# 150218_AriloRX_REV2_0_0.net
KiCad netlist of a schematic drawn in EAGLE
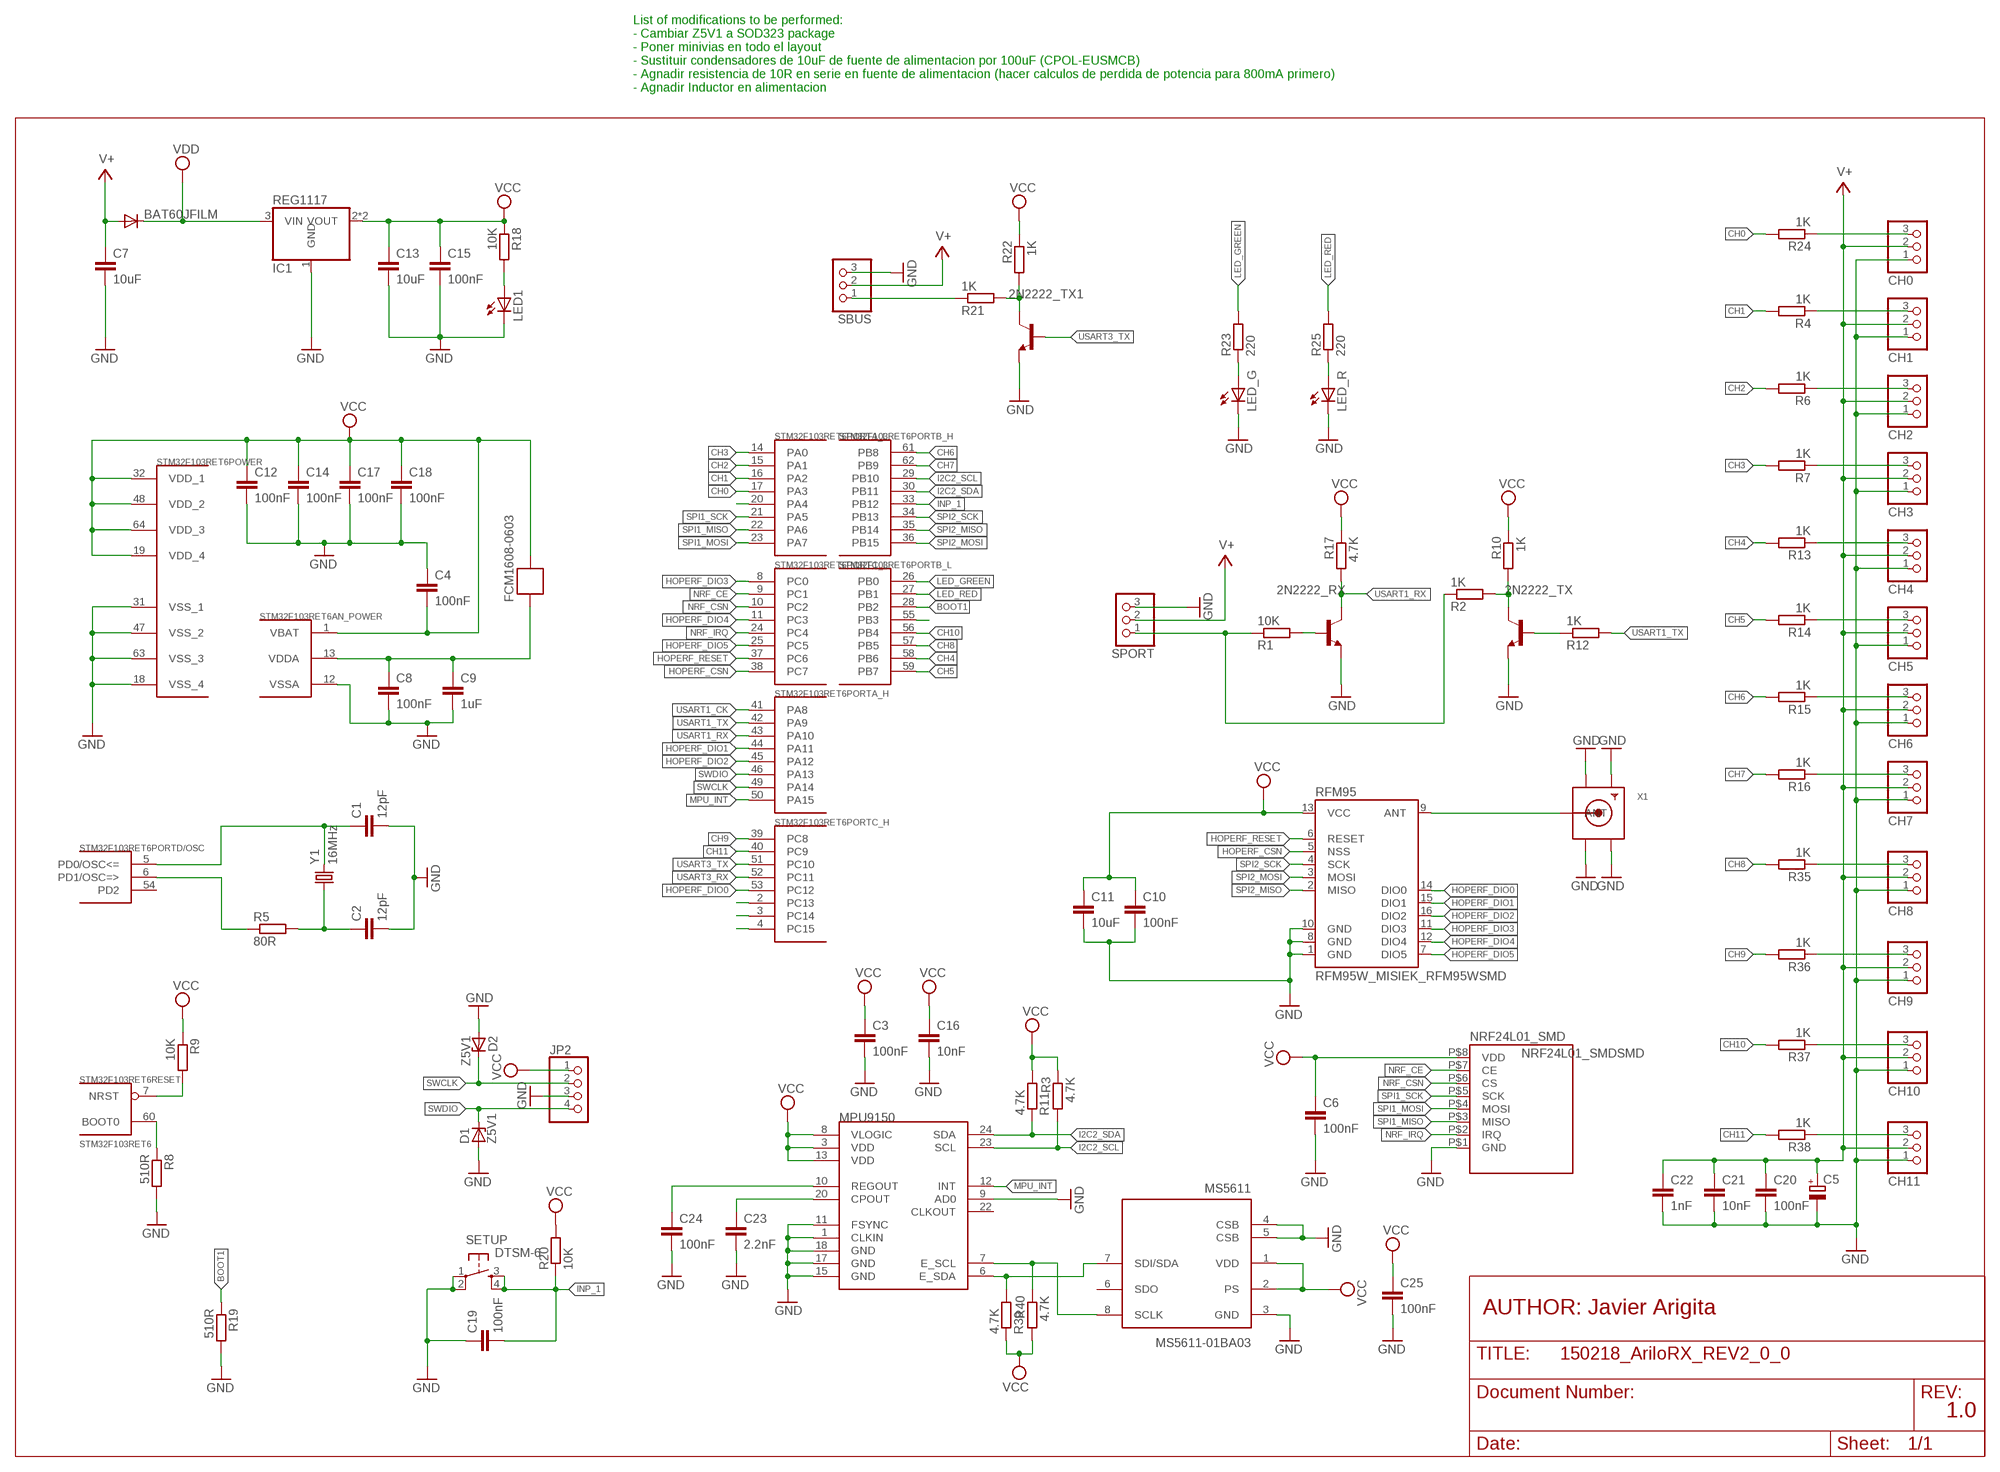
[diagram p0: schematic, sheet 1]

(export (version "E")
  (design (tool "Eeschema 10.0.6"))
  (components
    (comp (ref "2N2222_RX")
      (value "MMBT2222ALT1-NPN-SOT23-BEC")
      (footprint "eagle-import:SOT23-BEC")
      (libsource (lib "eagle-import") (part "-NPN-SOT23-BECMMBT2222ALT1"))
    )
    (comp (ref "2N2222_TX")
      (value "MMBT2222ALT1-NPN-SOT23-BEC")
      (footprint "eagle-import:SOT23-BEC")
      (libsource (lib "eagle-import") (part "-NPN-SOT23-BECMMBT2222ALT1"))
    )
    (comp (ref "2N2222_TX1")
      (value "MMBT2222ALT1-NPN-SOT23-BEC")
      (footprint "eagle-import:SOT23-BEC")
      (libsource (lib "eagle-import") (part "-NPN-SOT23-BECMMBT2222ALT1"))
    )
    (comp (ref "BAT60JFILM")
      (value "DIODE-SOD323-R")
      (footprint "eagle-import:SOD323-R")
      (libsource (lib "eagle-import") (part "DIODE-SOD323-R"))
    )
    (comp (ref "C1")
      (value "12pF")
      (footprint "eagle-import:RESISTOR_C0603")
      (libsource (lib "eagle-import") (part "RESISTOR_C-EUC0603"))
    )
    (comp (ref "C2")
      (value "12pF")
      (footprint "eagle-import:RESISTOR_C0603")
      (libsource (lib "eagle-import") (part "RESISTOR_C-EUC0603"))
    )
    (comp (ref "C3")
      (value "100nF")
      (footprint "eagle-import:RESISTOR_C0603")
      (libsource (lib "eagle-import") (part "RESISTOR_C-EUC0603"))
    )
    (comp (ref "C4")
      (value "100nF")
      (footprint "eagle-import:RESISTOR_C0603")
      (libsource (lib "eagle-import") (part "RESISTOR_C-EUC0603"))
    )
    (comp (ref "C5")
      (value "CPOL-EUSMCB")
      (footprint "eagle-import:SMC_B")
      (libsource (lib "eagle-import") (part "CPOL-EUSMCB"))
    )
    (comp (ref "C6")
      (value "100nF")
      (footprint "eagle-import:RESISTOR_C0603")
      (libsource (lib "eagle-import") (part "RESISTOR_C-EUC0603"))
    )
    (comp (ref "C7")
      (value "10uF")
      (footprint "eagle-import:RESISTOR_C3216")
      (libsource (lib "eagle-import") (part "RESISTOR_C-EUC3216"))
    )
    (comp (ref "C8")
      (value "100nF")
      (footprint "eagle-import:RESISTOR_C0603")
      (libsource (lib "eagle-import") (part "RESISTOR_C-EUC0603"))
    )
    (comp (ref "C9")
      (value "1uF")
      (footprint "eagle-import:RESISTOR_C0603")
      (libsource (lib "eagle-import") (part "RESISTOR_C-EUC0603"))
    )
    (comp (ref "C10")
      (value "100nF")
      (footprint "eagle-import:RESISTOR_C0603")
      (libsource (lib "eagle-import") (part "RESISTOR_C-EUC0603"))
    )
    (comp (ref "C11")
      (value "10uF")
      (footprint "eagle-import:RESISTOR_C3216")
      (libsource (lib "eagle-import") (part "RESISTOR_C-EUC3216"))
    )
    (comp (ref "C12")
      (value "100nF")
      (footprint "eagle-import:RESISTOR_C0603")
      (libsource (lib "eagle-import") (part "RESISTOR_C-EUC0603"))
    )
    (comp (ref "C13")
      (value "10uF")
      (footprint "eagle-import:RESISTOR_C3216")
      (libsource (lib "eagle-import") (part "RESISTOR_C-EUC3216"))
    )
    (comp (ref "C14")
      (value "100nF")
      (footprint "eagle-import:RESISTOR_C0603")
      (libsource (lib "eagle-import") (part "RESISTOR_C-EUC0603"))
    )
    (comp (ref "C15")
      (value "100nF")
      (footprint "eagle-import:RESISTOR_C0603")
      (libsource (lib "eagle-import") (part "RESISTOR_C-EUC0603"))
    )
    (comp (ref "C16")
      (value "10nF")
      (footprint "eagle-import:RESISTOR_C0603")
      (libsource (lib "eagle-import") (part "RESISTOR_C-EUC0603"))
    )
    (comp (ref "C17")
      (value "100nF")
      (footprint "eagle-import:RESISTOR_C0603")
      (libsource (lib "eagle-import") (part "RESISTOR_C-EUC0603"))
    )
    (comp (ref "C18")
      (value "100nF")
      (footprint "eagle-import:RESISTOR_C0603")
      (libsource (lib "eagle-import") (part "RESISTOR_C-EUC0603"))
    )
    (comp (ref "C19")
      (value "100nF")
      (footprint "eagle-import:RESISTOR_C0603")
      (libsource (lib "eagle-import") (part "RESISTOR_C-EUC0603"))
    )
    (comp (ref "C20")
      (value "100nF")
      (footprint "eagle-import:RESISTOR_C0603")
      (libsource (lib "eagle-import") (part "RESISTOR_C-EUC0603"))
    )
    (comp (ref "C21")
      (value "10nF")
      (footprint "eagle-import:RESISTOR_C0603")
      (libsource (lib "eagle-import") (part "RESISTOR_C-EUC0603"))
    )
    (comp (ref "C22")
      (value "1nF")
      (footprint "eagle-import:RESISTOR_C0603")
      (libsource (lib "eagle-import") (part "RESISTOR_C-EUC0603"))
    )
    (comp (ref "C23")
      (value "2.2nF")
      (footprint "eagle-import:RESISTOR_C0603")
      (libsource (lib "eagle-import") (part "RESISTOR_C-EUC0603"))
    )
    (comp (ref "C24")
      (value "100nF")
      (footprint "eagle-import:RESISTOR_C0603")
      (libsource (lib "eagle-import") (part "RESISTOR_C-EUC0603"))
    )
    (comp (ref "C25")
      (value "100nF")
      (footprint "eagle-import:RESISTOR_C0603")
      (libsource (lib "eagle-import") (part "RESISTOR_C-EUC0603"))
    )
    (comp (ref "CH0")
      (value "PINHD-1X3")
      (footprint "eagle-import:1X03")
      (libsource (lib "eagle-import") (part "pinhead_rc_PINHD-1X3"))
    )
    (comp (ref "CH1")
      (value "PINHD-1X3")
      (footprint "eagle-import:1X03")
      (libsource (lib "eagle-import") (part "pinhead_rc_PINHD-1X3"))
    )
    (comp (ref "CH2")
      (value "PINHD-1X3")
      (footprint "eagle-import:1X03")
      (libsource (lib "eagle-import") (part "pinhead_rc_PINHD-1X3"))
    )
    (comp (ref "CH3")
      (value "PINHD-1X3")
      (footprint "eagle-import:1X03")
      (libsource (lib "eagle-import") (part "pinhead_rc_PINHD-1X3"))
    )
    (comp (ref "CH4")
      (value "PINHD-1X3")
      (footprint "eagle-import:1X03")
      (libsource (lib "eagle-import") (part "pinhead_rc_PINHD-1X3"))
    )
    (comp (ref "CH5")
      (value "PINHD-1X3")
      (footprint "eagle-import:1X03")
      (libsource (lib "eagle-import") (part "pinhead_rc_PINHD-1X3"))
    )
    (comp (ref "CH6")
      (value "PINHD-1X3")
      (footprint "eagle-import:1X03")
      (libsource (lib "eagle-import") (part "pinhead_rc_PINHD-1X3"))
    )
    (comp (ref "CH7")
      (value "PINHD-1X3")
      (footprint "eagle-import:1X03")
      (libsource (lib "eagle-import") (part "pinhead_rc_PINHD-1X3"))
    )
    (comp (ref "CH8")
      (value "PINHD-1X3")
      (footprint "eagle-import:1X03")
      (libsource (lib "eagle-import") (part "pinhead_rc_PINHD-1X3"))
    )
    (comp (ref "CH9")
      (value "PINHD-1X3")
      (footprint "eagle-import:1X03")
      (libsource (lib "eagle-import") (part "pinhead_rc_PINHD-1X3"))
    )
    (comp (ref "CH10")
      (value "PINHD-1X3")
      (footprint "eagle-import:1X03")
      (libsource (lib "eagle-import") (part "pinhead_rc_PINHD-1X3"))
    )
    (comp (ref "CH11")
      (value "PINHD-1X3")
      (footprint "eagle-import:1X03")
      (libsource (lib "eagle-import") (part "pinhead_rc_PINHD-1X3"))
    )
    (comp (ref "D1")
      (value "Z5V1")
      (footprint "eagle-import:SOD80C")
      (libsource (lib "eagle-import") (part "ZENER-DIODESOD80C"))
    )
    (comp (ref "D2")
      (value "Z5V1")
      (footprint "eagle-import:SOD80C")
      (libsource (lib "eagle-import") (part "ZENER-DIODESOD80C"))
    )
    (comp (ref "FCM1608-0603")
      (value "FERRITE-BEAD")
      (footprint "eagle-import:R0603")
      (libsource (lib "eagle-import") (part "FERRITE-BEAD"))
    )
    (comp (ref "IC1")
      (value "REG1117")
      (footprint "eagle-import:SOT223")
      (libsource (lib "eagle-import") (part "REG1117"))
    )
    (comp (ref "JP2")
      (value "PINHD-1X4")
      (footprint "eagle-import:1X04")
      (libsource (lib "eagle-import") (part "PINHD-1X4"))
    )
    (comp (ref "LED1")
      (value "LED_LEDCHIP-LED0603")
      (footprint "eagle-import:LED_CHIP-LED0603")
      (libsource (lib "eagle-import") (part "LED_LEDCHIP-LED0603"))
    )
    (comp (ref "LED_G")
      (value "LEDCHIP-LED0603")
      (footprint "eagle-import:CHIP-LED0603")
      (libsource (lib "eagle-import") (part "LEDCHIP-LED0603"))
    )
    (comp (ref "LED_R")
      (value "LEDCHIP-LED0603")
      (footprint "eagle-import:CHIP-LED0603")
      (libsource (lib "eagle-import") (part "LEDCHIP-LED0603"))
    )
    (comp (ref "MPU9150")
      (value "MPU-9150QFN-24-NP")
      (footprint "eagle-import:QFN-24-NP")
      (libsource (lib "eagle-import") (part "MPU-9150QFN-24-NP"))
    )
    (comp (ref "MS5611")
      (value "MS5611-01BA03")
      (footprint "eagle-import:SON125P300X500X100-8N")
      (libsource (lib "eagle-import") (part "MS5611-01BA03"))
    )
    (comp (ref "NRF24L01_SMD")
      (value "NRF24L01_SMDSMD")
      (footprint "eagle-import:NRF24L01_SMD")
      (libsource (lib "eagle-import") (part "NRF24L01_SMDSMD"))
    )
    (comp (ref "R1")
      (value "10K")
      (footprint "eagle-import:RCL_R0603")
      (libsource (lib "eagle-import") (part "RCL_R-EU_R0603"))
    )
    (comp (ref "R2")
      (value "1K")
      (footprint "eagle-import:RCL_R0603")
      (libsource (lib "eagle-import") (part "RCL_R-EU_R0603"))
    )
    (comp (ref "R3")
      (value "4.7K")
      (footprint "eagle-import:RCL_R0603")
      (libsource (lib "eagle-import") (part "RCL_R-EU_R0603"))
    )
    (comp (ref "R4")
      (value "1K")
      (footprint "eagle-import:RCL_R0603")
      (libsource (lib "eagle-import") (part "RCL_R-EU_R0603"))
    )
    (comp (ref "R5")
      (value "80R")
      (footprint "eagle-import:RCL_R0603")
      (libsource (lib "eagle-import") (part "RCL_R-EU_R0603"))
    )
    (comp (ref "R6")
      (value "1K")
      (footprint "eagle-import:RCL_R0603")
      (libsource (lib "eagle-import") (part "RCL_R-EU_R0603"))
    )
    (comp (ref "R7")
      (value "1K")
      (footprint "eagle-import:RCL_R0603")
      (libsource (lib "eagle-import") (part "RCL_R-EU_R0603"))
    )
    (comp (ref "R8")
      (value "510R")
      (footprint "eagle-import:RCL_R0603")
      (libsource (lib "eagle-import") (part "RCL_R-EU_R0603"))
    )
    (comp (ref "R9")
      (value "10K")
      (footprint "eagle-import:RCL_R0603")
      (libsource (lib "eagle-import") (part "RCL_R-EU_R0603"))
    )
    (comp (ref "R10")
      (value "1K")
      (footprint "eagle-import:RCL_R0603")
      (libsource (lib "eagle-import") (part "RCL_R-EU_R0603"))
    )
    (comp (ref "R11")
      (value "4.7K")
      (footprint "eagle-import:RCL_R0603")
      (libsource (lib "eagle-import") (part "RCL_R-EU_R0603"))
    )
    (comp (ref "R12")
      (value "1K")
      (footprint "eagle-import:RCL_R0603")
      (libsource (lib "eagle-import") (part "RCL_R-EU_R0603"))
    )
    (comp (ref "R13")
      (value "1K")
      (footprint "eagle-import:RCL_R0603")
      (libsource (lib "eagle-import") (part "RCL_R-EU_R0603"))
    )
    (comp (ref "R14")
      (value "1K")
      (footprint "eagle-import:RCL_R0603")
      (libsource (lib "eagle-import") (part "RCL_R-EU_R0603"))
    )
    (comp (ref "R15")
      (value "1K")
      (footprint "eagle-import:RCL_R0603")
      (libsource (lib "eagle-import") (part "RCL_R-EU_R0603"))
    )
    (comp (ref "R16")
      (value "1K")
      (footprint "eagle-import:RCL_R0603")
      (libsource (lib "eagle-import") (part "RCL_R-EU_R0603"))
    )
    (comp (ref "R17")
      (value "4.7K")
      (footprint "eagle-import:RCL_R0603")
      (libsource (lib "eagle-import") (part "RCL_R-EU_R0603"))
    )
    (comp (ref "R18")
      (value "10K")
      (footprint "eagle-import:RCL_R0603")
      (libsource (lib "eagle-import") (part "RCL_R-EU_R0603"))
    )
    (comp (ref "R19")
      (value "510R")
      (footprint "eagle-import:RCL_R0603")
      (libsource (lib "eagle-import") (part "RCL_R-EU_R0603"))
    )
    (comp (ref "R20")
      (value "10K")
      (footprint "eagle-import:RCL_R0603")
      (libsource (lib "eagle-import") (part "RCL_R-EU_R0603"))
    )
    (comp (ref "R21")
      (value "1K")
      (footprint "eagle-import:RCL_R0603")
      (libsource (lib "eagle-import") (part "RCL_R-EU_R0603"))
    )
    (comp (ref "R22")
      (value "1K")
      (footprint "eagle-import:RCL_R0603")
      (libsource (lib "eagle-import") (part "RCL_R-EU_R0603"))
    )
    (comp (ref "R23")
      (value "220")
      (footprint "eagle-import:RCL_R0603")
      (libsource (lib "eagle-import") (part "RCL_R-EU_R0603"))
    )
    (comp (ref "R24")
      (value "1K")
      (footprint "eagle-import:RCL_R0603")
      (libsource (lib "eagle-import") (part "RCL_R-EU_R0603"))
    )
    (comp (ref "R25")
      (value "220")
      (footprint "eagle-import:RCL_R0603")
      (libsource (lib "eagle-import") (part "RCL_R-EU_R0603"))
    )
    (comp (ref "R35")
      (value "1K")
      (footprint "eagle-import:RCL_R0603")
      (libsource (lib "eagle-import") (part "RCL_R-EU_R0603"))
    )
    (comp (ref "R36")
      (value "1K")
      (footprint "eagle-import:RCL_R0603")
      (libsource (lib "eagle-import") (part "RCL_R-EU_R0603"))
    )
    (comp (ref "R37")
      (value "1K")
      (footprint "eagle-import:RCL_R0603")
      (libsource (lib "eagle-import") (part "RCL_R-EU_R0603"))
    )
    (comp (ref "R38")
      (value "1K")
      (footprint "eagle-import:RCL_R0603")
      (libsource (lib "eagle-import") (part "RCL_R-EU_R0603"))
    )
    (comp (ref "R39")
      (value "4.7K")
      (footprint "eagle-import:RCL_R0603")
      (libsource (lib "eagle-import") (part "RCL_R-EU_R0603"))
    )
    (comp (ref "R40")
      (value "4.7K")
      (footprint "eagle-import:RCL_R0603")
      (libsource (lib "eagle-import") (part "RCL_R-EU_R0603"))
    )
    (comp (ref "RFM95")
      (value "RFM95W_MISIEK_RFM95WSMD")
      (footprint "eagle-import:RFM95W_MISIEK_RFM95W_SMD")
      (libsource (lib "eagle-import") (part "RFM95W_MISIEK_RFM95WSMD"))
    )
    (comp (ref "SBUS")
      (value "PINHD-1X3")
      (footprint "eagle-import:1X03")
      (libsource (lib "eagle-import") (part "PINHD-1X3"))
    )
    (comp (ref "SETUP")
      (value "DTSM-6")
      (footprint "eagle-import:DTSM-6")
      (libsource (lib "eagle-import") (part "DTSM-6"))
    )
    (comp (ref "SPORT")
      (value "PINHD-1X3")
      (footprint "eagle-import:1X03")
      (libsource (lib "eagle-import") (part "PINHD-1X3"))
    )
    (comp (ref "STM32F103RET6")
      (value "STM32F103RET6")
      (footprint "eagle-import:TQFP64")
      (libsource (lib "eagle-import") (part "STM32F10XRXT6"))
    )
    (comp (ref "X1")
      (value "SMACONNECTOR_EDGE")
      (footprint "eagle-import:SMA_EDGELAUNCH")
      (libsource (lib "eagle-import") (part "SMACONNECTOR_EDGE"))
    )
    (comp (ref "Y1")
      (value "16MHz")
      (footprint "eagle-import:CRYSTAL-SMD-5X3")
      (libsource (lib "eagle-import") (part "CRYSTAL5X3"))
    )
  )
  (nets
    (net (code "1") (name "BOOT1") (class "Default")
      (node (ref "R19") (pin "1") (pinfunction "1_1") (pintype "passive"))
      (node (ref "STM32F103RET6") (pin "28") (pinfunction "PB2_28") (pintype "bidirectional"))
    )
    (net (code "2") (name "CH0") (class "Default")
      (node (ref "R24") (pin "2") (pinfunction "2_2") (pintype "passive"))
      (node (ref "STM32F103RET6") (pin "17") (pinfunction "PA3_17") (pintype "bidirectional"))
    )
    (net (code "3") (name "CH1") (class "Default")
      (node (ref "R4") (pin "2") (pinfunction "2_2") (pintype "passive"))
      (node (ref "STM32F103RET6") (pin "16") (pinfunction "PA2_16") (pintype "bidirectional"))
    )
    (net (code "4") (name "CH2") (class "Default")
      (node (ref "R6") (pin "2") (pinfunction "2_2") (pintype "passive"))
      (node (ref "STM32F103RET6") (pin "15") (pinfunction "PA1_15") (pintype "bidirectional"))
    )
    (net (code "5") (name "CH3") (class "Default")
      (node (ref "R7") (pin "2") (pinfunction "2_2") (pintype "passive"))
      (node (ref "STM32F103RET6") (pin "14") (pinfunction "PA0_14") (pintype "bidirectional"))
    )
    (net (code "6") (name "CH4") (class "Default")
      (node (ref "R13") (pin "2") (pinfunction "2_2") (pintype "passive"))
      (node (ref "STM32F103RET6") (pin "58") (pinfunction "PB6_58") (pintype "bidirectional"))
    )
    (net (code "7") (name "CH5") (class "Default")
      (node (ref "R14") (pin "2") (pinfunction "2_2") (pintype "passive"))
      (node (ref "STM32F103RET6") (pin "59") (pinfunction "PB7_59") (pintype "bidirectional"))
    )
    (net (code "8") (name "CH6") (class "Default")
      (node (ref "R15") (pin "2") (pinfunction "2_2") (pintype "passive"))
      (node (ref "STM32F103RET6") (pin "61") (pinfunction "PB8_61") (pintype "bidirectional"))
    )
    (net (code "9") (name "CH7") (class "Default")
      (node (ref "R16") (pin "2") (pinfunction "2_2") (pintype "passive"))
      (node (ref "STM32F103RET6") (pin "62") (pinfunction "PB9_62") (pintype "bidirectional"))
    )
    (net (code "10") (name "CH8") (class "Default")
      (node (ref "R35") (pin "2") (pinfunction "2_2") (pintype "passive"))
      (node (ref "STM32F103RET6") (pin "57") (pinfunction "PB5_57") (pintype "bidirectional"))
    )
    (net (code "11") (name "CH9") (class "Default")
      (node (ref "R36") (pin "2") (pinfunction "2_2") (pintype "passive"))
      (node (ref "STM32F103RET6") (pin "39") (pinfunction "PC8_39") (pintype "bidirectional"))
    )
    (net (code "12") (name "CH10") (class "Default")
      (node (ref "R37") (pin "2") (pinfunction "2_2") (pintype "passive"))
      (node (ref "STM32F103RET6") (pin "56") (pinfunction "PB4_56") (pintype "bidirectional"))
    )
    (net (code "13") (name "CH11") (class "Default")
      (node (ref "R38") (pin "2") (pinfunction "2_2") (pintype "passive"))
      (node (ref "STM32F103RET6") (pin "40") (pinfunction "PC9_40") (pintype "bidirectional"))
    )
    (net (code "14") (name "GND") (class "Default")
      (node (ref "2N2222_RX") (pin "E") (pinfunction "E_E") (pintype "passive"))
      (node (ref "2N2222_TX") (pin "E") (pinfunction "E_E") (pintype "passive"))
      (node (ref "2N2222_TX1") (pin "E") (pinfunction "E_E") (pintype "passive"))
      (node (ref "C1") (pin "2") (pinfunction "2_2") (pintype "passive"))
      (node (ref "C10") (pin "2") (pinfunction "2_2") (pintype "passive"))
      (node (ref "C11") (pin "2") (pinfunction "2_2") (pintype "passive"))
      (node (ref "C12") (pin "2") (pinfunction "2_2") (pintype "passive"))
      (node (ref "C13") (pin "2") (pinfunction "2_2") (pintype "passive"))
      (node (ref "C14") (pin "2") (pinfunction "2_2") (pintype "passive"))
      (node (ref "C15") (pin "2") (pinfunction "2_2") (pintype "passive"))
      (node (ref "C16") (pin "2") (pinfunction "2_2") (pintype "passive"))
      (node (ref "C17") (pin "2") (pinfunction "2_2") (pintype "passive"))
      (node (ref "C18") (pin "2") (pinfunction "2_2") (pintype "passive"))
      (node (ref "C19") (pin "1") (pinfunction "1_1") (pintype "passive"))
      (node (ref "C2") (pin "2") (pinfunction "2_2") (pintype "passive"))
      (node (ref "C20") (pin "2") (pinfunction "2_2") (pintype "passive"))
      (node (ref "C21") (pin "2") (pinfunction "2_2") (pintype "passive"))
      (node (ref "C22") (pin "2") (pinfunction "2_2") (pintype "passive"))
      (node (ref "C23") (pin "2") (pinfunction "2_2") (pintype "passive"))
      (node (ref "C24") (pin "2") (pinfunction "2_2") (pintype "passive"))
      (node (ref "C25") (pin "2") (pinfunction "2_2") (pintype "passive"))
      (node (ref "C3") (pin "2") (pinfunction "2_2") (pintype "passive"))
      (node (ref "C4") (pin "1") (pinfunction "1_1") (pintype "passive"))
      (node (ref "C5") (pin "-") (pinfunction "-_-") (pintype "passive"))
      (node (ref "C6") (pin "2") (pinfunction "2_2") (pintype "passive"))
      (node (ref "C7") (pin "2") (pinfunction "2_2") (pintype "passive"))
      (node (ref "C8") (pin "2") (pinfunction "2_2") (pintype "passive"))
      (node (ref "C9") (pin "2") (pinfunction "2_2") (pintype "passive"))
      (node (ref "CH0") (pin "1") (pinfunction "1_1") (pintype "passive"))
      (node (ref "CH1") (pin "1") (pinfunction "1_1") (pintype "passive"))
      (node (ref "CH10") (pin "1") (pinfunction "1_1") (pintype "passive"))
      (node (ref "CH11") (pin "1") (pinfunction "1_1") (pintype "passive"))
      (node (ref "CH2") (pin "1") (pinfunction "1_1") (pintype "passive"))
      (node (ref "CH3") (pin "1") (pinfunction "1_1") (pintype "passive"))
      (node (ref "CH4") (pin "1") (pinfunction "1_1") (pintype "passive"))
      (node (ref "CH5") (pin "1") (pinfunction "1_1") (pintype "passive"))
      (node (ref "CH6") (pin "1") (pinfunction "1_1") (pintype "passive"))
      (node (ref "CH7") (pin "1") (pinfunction "1_1") (pintype "passive"))
      (node (ref "CH8") (pin "1") (pinfunction "1_1") (pintype "passive"))
      (node (ref "CH9") (pin "1") (pinfunction "1_1") (pintype "passive"))
      (node (ref "D1") (pin "A") (pinfunction "A_A") (pintype "passive"))
      (node (ref "D2") (pin "A") (pinfunction "A_A") (pintype "passive"))
      (node (ref "IC1") (pin "1") (pinfunction "GND_1") (pintype "power_in"))
      (node (ref "JP2") (pin "3") (pinfunction "3_3") (pintype "passive"))
      (node (ref "LED1") (pin "C") (pinfunction "C_C") (pintype "passive"))
      (node (ref "LED_G") (pin "C") (pinfunction "C_C") (pintype "passive"))
      (node (ref "LED_R") (pin "C") (pinfunction "C_C") (pintype "passive"))
      (node (ref "MPU9150") (pin "1") (pinfunction "CLKIN_1") (pintype "bidirectional"))
      (node (ref "MPU9150") (pin "11") (pinfunction "FSYNC_11") (pintype "bidirectional"))
      (node (ref "MPU9150") (pin "15") (pinfunction "GND_15") (pintype "bidirectional"))
      (node (ref "MPU9150") (pin "17") (pinfunction "GND_17") (pintype "bidirectional"))
      (node (ref "MPU9150") (pin "18") (pinfunction "GND_18") (pintype "bidirectional"))
      (node (ref "MPU9150") (pin "9") (pinfunction "AD0_9") (pintype "bidirectional"))
      (node (ref "MS5611") (pin "3") (pinfunction "GND_3") (pintype "power_in"))
      (node (ref "MS5611") (pin "4") (pinfunction "CSB_4") (pintype "input"))
      (node (ref "MS5611") (pin "5") (pinfunction "CSB_5") (pintype "input"))
      (node (ref "NRF24L01_SMD") (pin "P$1") (pinfunction "GND_P$1") (pintype "power_in"))
      (node (ref "R19") (pin "2") (pinfunction "2_2") (pintype "passive"))
      (node (ref "R8") (pin "2") (pinfunction "2_2") (pintype "passive"))
      (node (ref "RFM95") (pin "1") (pinfunction "GND_1") (pintype "power_in"))
      (node (ref "RFM95") (pin "10") (pinfunction "GND_10") (pintype "power_in"))
      (node (ref "RFM95") (pin "8") (pinfunction "GND_8") (pintype "power_in"))
      (node (ref "SBUS") (pin "3") (pinfunction "3_3") (pintype "passive"))
      (node (ref "SETUP") (pin "1") (pinfunction "1_1") (pintype "passive"))
      (node (ref "SETUP") (pin "2") (pinfunction "2_2") (pintype "passive"))
      (node (ref "SPORT") (pin "3") (pinfunction "3_3") (pintype "passive"))
      (node (ref "STM32F103RET6") (pin "12") (pinfunction "VSSA_12") (pintype "power_in"))
      (node (ref "STM32F103RET6") (pin "18") (pinfunction "VSS_4_18") (pintype "power_in"))
      (node (ref "STM32F103RET6") (pin "31") (pinfunction "VSS_1_31") (pintype "power_in"))
      (node (ref "STM32F103RET6") (pin "47") (pinfunction "VSS_2_47") (pintype "power_in"))
      (node (ref "STM32F103RET6") (pin "63") (pinfunction "VSS_3_63") (pintype "power_in"))
      (node (ref "X1") (pin "GND@1") (pinfunction "GND4_GND@1") (pintype "power_in"))
      (node (ref "X1") (pin "GND@2") (pinfunction "GND3_GND@2") (pintype "power_in"))
      (node (ref "X1") (pin "GND@3") (pinfunction "GND2_GND@3") (pintype "power_in"))
      (node (ref "X1") (pin "GND@4") (pinfunction "GND1_GND@4") (pintype "power_in"))
    )
    (net (code "15") (name "HOPERF_CSN") (class "Default")
      (node (ref "RFM95") (pin "5") (pinfunction "NSS_5") (pintype "input"))
      (node (ref "STM32F103RET6") (pin "38") (pinfunction "PC7_38") (pintype "bidirectional"))
    )
    (net (code "16") (name "HOPERF_DIO0") (class "Default")
      (node (ref "RFM95") (pin "14") (pinfunction "DIO0_14") (pintype "input"))
      (node (ref "STM32F103RET6") (pin "53") (pinfunction "PC12_53") (pintype "bidirectional"))
    )
    (net (code "17") (name "HOPERF_DIO1") (class "Default")
      (node (ref "RFM95") (pin "15") (pinfunction "DIO1_15") (pintype "input"))
      (node (ref "STM32F103RET6") (pin "44") (pinfunction "PA11_44") (pintype "bidirectional"))
    )
    (net (code "18") (name "HOPERF_DIO2") (class "Default")
      (node (ref "RFM95") (pin "16") (pinfunction "DIO2_16") (pintype "input"))
      (node (ref "STM32F103RET6") (pin "45") (pinfunction "PA12_45") (pintype "bidirectional"))
    )
    (net (code "19") (name "HOPERF_DIO3") (class "Default")
      (node (ref "RFM95") (pin "11") (pinfunction "DIO3_11") (pintype "bidirectional"))
      (node (ref "STM32F103RET6") (pin "8") (pinfunction "PC0_8") (pintype "bidirectional"))
    )
    (net (code "20") (name "HOPERF_DIO4") (class "Default")
      (node (ref "RFM95") (pin "12") (pinfunction "DIO4_12") (pintype "bidirectional"))
      (node (ref "STM32F103RET6") (pin "11") (pinfunction "PC3_11") (pintype "bidirectional"))
    )
    (net (code "21") (name "HOPERF_DIO5") (class "Default")
      (node (ref "RFM95") (pin "7") (pinfunction "DIO5_7") (pintype "bidirectional"))
      (node (ref "STM32F103RET6") (pin "25") (pinfunction "PC5_25") (pintype "bidirectional"))
    )
    (net (code "22") (name "HOPERF_RESET") (class "Default")
      (node (ref "RFM95") (pin "6") (pinfunction "RESET_6") (pintype "output"))
      (node (ref "STM32F103RET6") (pin "37") (pinfunction "PC6_37") (pintype "bidirectional"))
    )
    (net (code "23") (name "I2C2_SCL") (class "Default")
      (node (ref "MPU9150") (pin "23") (pinfunction "SCL_23") (pintype "bidirectional"))
      (node (ref "R3") (pin "2") (pinfunction "2_2") (pintype "passive"))
      (node (ref "STM32F103RET6") (pin "29") (pinfunction "PB10_29") (pintype "bidirectional"))
    )
    (net (code "24") (name "I2C2_SDA") (class "Default")
      (node (ref "MPU9150") (pin "24") (pinfunction "SDA_24") (pintype "bidirectional"))
      (node (ref "R11") (pin "1") (pinfunction "1_1") (pintype "passive"))
      (node (ref "STM32F103RET6") (pin "30") (pinfunction "PB11_30") (pintype "bidirectional"))
    )
    (net (code "25") (name "INP_1") (class "Default")
      (node (ref "C19") (pin "2") (pinfunction "2_2") (pintype "passive"))
      (node (ref "R20") (pin "1") (pinfunction "1_1") (pintype "passive"))
      (node (ref "SETUP") (pin "3") (pinfunction "3_3") (pintype "passive"))
      (node (ref "SETUP") (pin "4") (pinfunction "4_4") (pintype "passive"))
      (node (ref "STM32F103RET6") (pin "33") (pinfunction "PB12_33") (pintype "bidirectional"))
    )
    (net (code "26") (name "LED_GREEN") (class "Default")
      (node (ref "R23") (pin "2") (pinfunction "2_2") (pintype "passive"))
      (node (ref "STM32F103RET6") (pin "26") (pinfunction "PB0_26") (pintype "bidirectional"))
    )
    (net (code "27") (name "LED_RED") (class "Default")
      (node (ref "R25") (pin "2") (pinfunction "2_2") (pintype "passive"))
      (node (ref "STM32F103RET6") (pin "27") (pinfunction "PB1_27") (pintype "bidirectional"))
    )
    (net (code "28") (name "MPU_INT") (class "Default")
      (node (ref "MPU9150") (pin "12") (pinfunction "INT_12") (pintype "bidirectional"))
      (node (ref "STM32F103RET6") (pin "50") (pinfunction "PA15_50") (pintype "bidirectional"))
    )
    (net (code "29") (name "NRF_CE") (class "Default")
      (node (ref "NRF24L01_SMD") (pin "P$7") (pinfunction "CE_P$7") (pintype "input"))
      (node (ref "STM32F103RET6") (pin "9") (pinfunction "PC1_9") (pintype "bidirectional"))
    )
    (net (code "30") (name "NRF_CSN") (class "Default")
      (node (ref "NRF24L01_SMD") (pin "P$6") (pinfunction "CS_P$6") (pintype "input"))
      (node (ref "STM32F103RET6") (pin "10") (pinfunction "PC2_10") (pintype "bidirectional"))
    )
    (net (code "31") (name "NRF_IRQ") (class "Default")
      (node (ref "NRF24L01_SMD") (pin "P$2") (pinfunction "IRQ_P$2") (pintype "output"))
      (node (ref "STM32F103RET6") (pin "24") (pinfunction "PC4_24") (pintype "bidirectional"))
    )
    (net (code "32") (name "Net-(2N2222_RX-PadB)") (class "Default")
      (node (ref "2N2222_RX") (pin "B") (pinfunction "B_B") (pintype "passive"))
      (node (ref "R1") (pin "2") (pinfunction "2_2") (pintype "passive"))
    )
    (net (code "33") (name "Net-(2N2222_TX-PadB)") (class "Default")
      (node (ref "2N2222_TX") (pin "B") (pinfunction "B_B") (pintype "passive"))
      (node (ref "R12") (pin "1") (pinfunction "1_1") (pintype "passive"))
    )
    (net (code "34") (name "Net-(2N2222_TX-PadC)") (class "Default")
      (node (ref "2N2222_TX") (pin "C") (pinfunction "C_C") (pintype "passive"))
      (node (ref "R10") (pin "2") (pinfunction "2_2") (pintype "passive"))
      (node (ref "R2") (pin "2") (pinfunction "2_2") (pintype "passive"))
    )
    (net (code "35") (name "Net-(2N2222_TX1-PadC)") (class "Default")
      (node (ref "2N2222_TX1") (pin "C") (pinfunction "C_C") (pintype "passive"))
      (node (ref "R21") (pin "2") (pinfunction "2_2") (pintype "passive"))
      (node (ref "R22") (pin "2") (pinfunction "2_2") (pintype "passive"))
    )
    (net (code "36") (name "Net-(C2-Pad1)") (class "Default")
      (node (ref "C2") (pin "1") (pinfunction "1_1") (pintype "passive"))
      (node (ref "R5") (pin "2") (pinfunction "2_2") (pintype "passive"))
      (node (ref "Y1") (pin "1") (pinfunction "1_1") (pintype "passive"))
    )
    (net (code "37") (name "Net-(CH0-Pad3)") (class "Default")
      (node (ref "CH0") (pin "3") (pinfunction "3_3") (pintype "passive"))
      (node (ref "R24") (pin "1") (pinfunction "1_1") (pintype "passive"))
    )
    (net (code "38") (name "Net-(CH1-Pad3)") (class "Default")
      (node (ref "CH1") (pin "3") (pinfunction "3_3") (pintype "passive"))
      (node (ref "R4") (pin "1") (pinfunction "1_1") (pintype "passive"))
    )
    (net (code "39") (name "Net-(CH2-Pad3)") (class "Default")
      (node (ref "CH2") (pin "3") (pinfunction "3_3") (pintype "passive"))
      (node (ref "R6") (pin "1") (pinfunction "1_1") (pintype "passive"))
    )
    (net (code "40") (name "Net-(CH3-Pad3)") (class "Default")
      (node (ref "CH3") (pin "3") (pinfunction "3_3") (pintype "passive"))
      (node (ref "R7") (pin "1") (pinfunction "1_1") (pintype "passive"))
    )
    (net (code "41") (name "Net-(CH4-Pad3)") (class "Default")
      (node (ref "CH4") (pin "3") (pinfunction "3_3") (pintype "passive"))
      (node (ref "R13") (pin "1") (pinfunction "1_1") (pintype "passive"))
    )
    (net (code "42") (name "Net-(CH5-Pad3)") (class "Default")
      (node (ref "CH5") (pin "3") (pinfunction "3_3") (pintype "passive"))
      (node (ref "R14") (pin "1") (pinfunction "1_1") (pintype "passive"))
    )
    (net (code "43") (name "Net-(CH6-Pad3)") (class "Default")
      (node (ref "CH6") (pin "3") (pinfunction "3_3") (pintype "passive"))
      (node (ref "R15") (pin "1") (pinfunction "1_1") (pintype "passive"))
    )
    (net (code "44") (name "Net-(CH7-Pad3)") (class "Default")
      (node (ref "CH7") (pin "3") (pinfunction "3_3") (pintype "passive"))
      (node (ref "R16") (pin "1") (pinfunction "1_1") (pintype "passive"))
    )
    (net (code "45") (name "Net-(CH8-Pad3)") (class "Default")
      (node (ref "CH8") (pin "3") (pinfunction "3_3") (pintype "passive"))
      (node (ref "R35") (pin "1") (pinfunction "1_1") (pintype "passive"))
    )
    (net (code "46") (name "Net-(CH9-Pad3)") (class "Default")
      (node (ref "CH9") (pin "3") (pinfunction "3_3") (pintype "passive"))
      (node (ref "R36") (pin "1") (pinfunction "1_1") (pintype "passive"))
    )
    (net (code "47") (name "Net-(CH10-Pad3)") (class "Default")
      (node (ref "CH10") (pin "3") (pinfunction "3_3") (pintype "passive"))
      (node (ref "R37") (pin "1") (pinfunction "1_1") (pintype "passive"))
    )
    (net (code "48") (name "Net-(CH11-Pad3)") (class "Default")
      (node (ref "CH11") (pin "3") (pinfunction "3_3") (pintype "passive"))
      (node (ref "R38") (pin "1") (pinfunction "1_1") (pintype "passive"))
    )
    (net (code "49") (name "Net-(FCM1608-0603-P$2)") (class "Default")
      (node (ref "C8") (pin "1") (pinfunction "1_1") (pintype "passive"))
      (node (ref "C9") (pin "1") (pinfunction "1_1") (pintype "passive"))
      (node (ref "FCM1608-0603") (pin "2") (pinfunction "P$2_2") (pintype "bidirectional"))
      (node (ref "STM32F103RET6") (pin "13") (pinfunction "VDDA_13") (pintype "power_in"))
    )
    (net (code "50") (name "Net-(LED1-PadA)") (class "Default")
      (node (ref "LED1") (pin "A") (pinfunction "A_A") (pintype "passive"))
      (node (ref "R18") (pin "2") (pinfunction "2_2") (pintype "passive"))
    )
    (net (code "51") (name "Net-(LED_G-PadA)") (class "Default")
      (node (ref "LED_G") (pin "A") (pinfunction "A_A") (pintype "passive"))
      (node (ref "R23") (pin "1") (pinfunction "1_1") (pintype "passive"))
    )
    (net (code "52") (name "Net-(LED_R-PadA)") (class "Default")
      (node (ref "LED_R") (pin "A") (pinfunction "A_A") (pintype "passive"))
      (node (ref "R25") (pin "1") (pinfunction "1_1") (pintype "passive"))
    )
    (net (code "53") (name "Net-(MPU9150-CPOUT)") (class "Default")
      (node (ref "C23") (pin "1") (pinfunction "1_1") (pintype "passive"))
      (node (ref "MPU9150") (pin "20") (pinfunction "CPOUT_20") (pintype "bidirectional"))
    )
    (net (code "54") (name "Net-(MPU9150-E_SCL)") (class "Default")
      (node (ref "MPU9150") (pin "7") (pinfunction "E_SCL_7") (pintype "bidirectional"))
      (node (ref "MS5611") (pin "8") (pinfunction "SCLK_8") (pintype "input"))
      (node (ref "R40") (pin "1") (pinfunction "1_1") (pintype "passive"))
    )
    (net (code "55") (name "Net-(MPU9150-E_SDA)") (class "Default")
      (node (ref "MPU9150") (pin "6") (pinfunction "E_SDA_6") (pintype "bidirectional"))
      (node (ref "MS5611") (pin "7") (pinfunction "SDI/SDA_7") (pintype "bidirectional"))
      (node (ref "R39") (pin "2") (pinfunction "2_2") (pintype "passive"))
    )
    (net (code "56") (name "Net-(MPU9150-REGOUT)") (class "Default")
      (node (ref "C24") (pin "1") (pinfunction "1_1") (pintype "passive"))
      (node (ref "MPU9150") (pin "10") (pinfunction "REGOUT_10") (pintype "bidirectional"))
    )
    (net (code "57") (name "Net-(R1-Pad1)") (class "Default")
      (node (ref "R1") (pin "1") (pinfunction "1_1") (pintype "passive"))
      (node (ref "R2") (pin "1") (pinfunction "1_1") (pintype "passive"))
      (node (ref "SPORT") (pin "1") (pinfunction "1_1") (pintype "passive"))
    )
    (net (code "58") (name "Net-(R21-Pad1)") (class "Default")
      (node (ref "R21") (pin "1") (pinfunction "1_1") (pintype "passive"))
      (node (ref "SBUS") (pin "1") (pinfunction "1_1") (pintype "passive"))
    )
    (net (code "59") (name "Net-(RFM95-ANT)") (class "Default")
      (node (ref "RFM95") (pin "9") (pinfunction "ANT_9") (pintype "bidirectional"))
      (node (ref "X1") (pin "P") (pinfunction "ANT_P") (pintype "bidirectional"))
    )
    (net (code "60") (name "Net-(STM32F103RET6H-PD0{slash}OSC<=)") (class "Default")
      (node (ref "C1") (pin "1") (pinfunction "1_1") (pintype "passive"))
      (node (ref "STM32F103RET6") (pin "5") (pinfunction "PD0/OSC<=_5") (pintype "bidirectional"))
      (node (ref "Y1") (pin "3") (pinfunction "2_3") (pintype "passive"))
    )
    (net (code "61") (name "Net-(STM32F103RET6H-PD1{slash}OSC=>)") (class "Default")
      (node (ref "R5") (pin "1") (pinfunction "1_1") (pintype "passive"))
      (node (ref "STM32F103RET6") (pin "6") (pinfunction "PD1/OSC=>_6") (pintype "bidirectional"))
    )
    (net (code "62") (name "Net-(STM32F103RET6J-BOOT0)") (class "Default")
      (node (ref "R8") (pin "1") (pinfunction "1_1") (pintype "passive"))
      (node (ref "STM32F103RET6") (pin "60") (pinfunction "BOOT0_60") (pintype "input"))
    )
    (net (code "63") (name "Net-(STM32F103RET6J-NRST)") (class "Default")
      (node (ref "R9") (pin "2") (pinfunction "2_2") (pintype "passive"))
      (node (ref "STM32F103RET6") (pin "7") (pinfunction "NRST_7") (pintype "input"))
    )
    (net (code "64") (name "SPI1_MISO") (class "Default")
      (node (ref "NRF24L01_SMD") (pin "P$3") (pinfunction "MISO_P$3") (pintype "output"))
      (node (ref "STM32F103RET6") (pin "22") (pinfunction "PA6_22") (pintype "bidirectional"))
    )
    (net (code "65") (name "SPI1_MOSI") (class "Default")
      (node (ref "NRF24L01_SMD") (pin "P$4") (pinfunction "MOSI_P$4") (pintype "input"))
      (node (ref "STM32F103RET6") (pin "23") (pinfunction "PA7_23") (pintype "bidirectional"))
    )
    (net (code "66") (name "SPI1_SCK") (class "Default")
      (node (ref "NRF24L01_SMD") (pin "P$5") (pinfunction "SCK_P$5") (pintype "input"))
      (node (ref "STM32F103RET6") (pin "21") (pinfunction "PA5_21") (pintype "bidirectional"))
    )
    (net (code "67") (name "SPI2_MISO") (class "Default")
      (node (ref "RFM95") (pin "2") (pinfunction "MISO_2") (pintype "output"))
      (node (ref "STM32F103RET6") (pin "35") (pinfunction "PB14_35") (pintype "bidirectional"))
    )
    (net (code "68") (name "SPI2_MOSI") (class "Default")
      (node (ref "RFM95") (pin "3") (pinfunction "MOSI_3") (pintype "input"))
      (node (ref "STM32F103RET6") (pin "36") (pinfunction "PB15_36") (pintype "bidirectional"))
    )
    (net (code "69") (name "SPI2_SCK") (class "Default")
      (node (ref "RFM95") (pin "4") (pinfunction "SCK_4") (pintype "input"))
      (node (ref "STM32F103RET6") (pin "34") (pinfunction "PB13_34") (pintype "bidirectional"))
    )
    (net (code "70") (name "SWCLK") (class "Default")
      (node (ref "D2") (pin "C") (pinfunction "C_C") (pintype "passive"))
      (node (ref "JP2") (pin "2") (pinfunction "2_2") (pintype "passive"))
      (node (ref "STM32F103RET6") (pin "49") (pinfunction "PA14_49") (pintype "bidirectional"))
    )
    (net (code "71") (name "SWDIO") (class "Default")
      (node (ref "D1") (pin "C") (pinfunction "C_C") (pintype "passive"))
      (node (ref "JP2") (pin "4") (pinfunction "4_4") (pintype "passive"))
      (node (ref "STM32F103RET6") (pin "46") (pinfunction "PA13_46") (pintype "bidirectional"))
    )
    (net (code "72") (name "USART1_CK") (class "Default")
      (node (ref "STM32F103RET6") (pin "41") (pinfunction "PA8_41") (pintype "bidirectional"))
    )
    (net (code "73") (name "USART1_RX") (class "Default")
      (node (ref "2N2222_RX") (pin "C") (pinfunction "C_C") (pintype "passive"))
      (node (ref "R17") (pin "2") (pinfunction "2_2") (pintype "passive"))
      (node (ref "STM32F103RET6") (pin "43") (pinfunction "PA10_43") (pintype "bidirectional"))
    )
    (net (code "74") (name "USART1_TX") (class "Default")
      (node (ref "R12") (pin "2") (pinfunction "2_2") (pintype "passive"))
      (node (ref "STM32F103RET6") (pin "42") (pinfunction "PA9_42") (pintype "bidirectional"))
    )
    (net (code "75") (name "USART3_RX") (class "Default")
      (node (ref "STM32F103RET6") (pin "52") (pinfunction "PC11_52") (pintype "bidirectional"))
    )
    (net (code "76") (name "USART3_TX") (class "Default")
      (node (ref "2N2222_TX1") (pin "B") (pinfunction "B_B") (pintype "passive"))
      (node (ref "STM32F103RET6") (pin "51") (pinfunction "PC10_51") (pintype "bidirectional"))
    )
    (net (code "77") (name "V+") (class "Default")
      (node (ref "BAT60JFILM") (pin "A") (pinfunction "A_A") (pintype "passive"))
      (node (ref "C20") (pin "1") (pinfunction "1_1") (pintype "passive"))
      (node (ref "C21") (pin "1") (pinfunction "1_1") (pintype "passive"))
      (node (ref "C22") (pin "1") (pinfunction "1_1") (pintype "passive"))
      (node (ref "C5") (pin "+") (pinfunction "+_+") (pintype "passive"))
      (node (ref "C7") (pin "1") (pinfunction "1_1") (pintype "passive"))
      (node (ref "CH0") (pin "2") (pinfunction "2_2") (pintype "passive"))
      (node (ref "CH1") (pin "2") (pinfunction "2_2") (pintype "passive"))
      (node (ref "CH10") (pin "2") (pinfunction "2_2") (pintype "passive"))
      (node (ref "CH11") (pin "2") (pinfunction "2_2") (pintype "passive"))
      (node (ref "CH2") (pin "2") (pinfunction "2_2") (pintype "passive"))
      (node (ref "CH3") (pin "2") (pinfunction "2_2") (pintype "passive"))
      (node (ref "CH4") (pin "2") (pinfunction "2_2") (pintype "passive"))
      (node (ref "CH5") (pin "2") (pinfunction "2_2") (pintype "passive"))
      (node (ref "CH6") (pin "2") (pinfunction "2_2") (pintype "passive"))
      (node (ref "CH7") (pin "2") (pinfunction "2_2") (pintype "passive"))
      (node (ref "CH8") (pin "2") (pinfunction "2_2") (pintype "passive"))
      (node (ref "CH9") (pin "2") (pinfunction "2_2") (pintype "passive"))
      (node (ref "SBUS") (pin "2") (pinfunction "2_2") (pintype "passive"))
      (node (ref "SPORT") (pin "2") (pinfunction "2_2") (pintype "passive"))
    )
    (net (code "78") (name "VCC") (class "Default")
      (node (ref "C10") (pin "1") (pinfunction "1_1") (pintype "passive"))
      (node (ref "C11") (pin "1") (pinfunction "1_1") (pintype "passive"))
      (node (ref "C12") (pin "1") (pinfunction "1_1") (pintype "passive"))
      (node (ref "C13") (pin "1") (pinfunction "1_1") (pintype "passive"))
      (node (ref "C14") (pin "1") (pinfunction "1_1") (pintype "passive"))
      (node (ref "C15") (pin "1") (pinfunction "1_1") (pintype "passive"))
      (node (ref "C16") (pin "1") (pinfunction "1_1") (pintype "passive"))
      (node (ref "C17") (pin "1") (pinfunction "1_1") (pintype "passive"))
      (node (ref "C18") (pin "1") (pinfunction "1_1") (pintype "passive"))
      (node (ref "C25") (pin "1") (pinfunction "1_1") (pintype "passive"))
      (node (ref "C3") (pin "1") (pinfunction "1_1") (pintype "passive"))
      (node (ref "C4") (pin "2") (pinfunction "2_2") (pintype "passive"))
      (node (ref "C6") (pin "1") (pinfunction "1_1") (pintype "passive"))
      (node (ref "FCM1608-0603") (pin "1") (pinfunction "P$1_1") (pintype "bidirectional"))
      (node (ref "IC1") (pin "2") (pinfunction "VOUT_2") (pintype "power_in"))
      (node (ref "IC1") (pin "4") (pinfunction "VOUT_4") (pintype "power_in"))
      (node (ref "JP2") (pin "1") (pinfunction "1_1") (pintype "passive"))
      (node (ref "MPU9150") (pin "13") (pinfunction "VDD_13") (pintype "bidirectional"))
      (node (ref "MPU9150") (pin "3") (pinfunction "VDD_3") (pintype "bidirectional"))
      (node (ref "MPU9150") (pin "8") (pinfunction "VLOGIC_8") (pintype "bidirectional"))
      (node (ref "MS5611") (pin "1") (pinfunction "VDD_1") (pintype "power_in"))
      (node (ref "MS5611") (pin "2") (pinfunction "PS_2") (pintype "input"))
      (node (ref "NRF24L01_SMD") (pin "P$8") (pinfunction "VDD_P$8") (pintype "bidirectional"))
      (node (ref "R10") (pin "1") (pinfunction "1_1") (pintype "passive"))
      (node (ref "R11") (pin "2") (pinfunction "2_2") (pintype "passive"))
      (node (ref "R17") (pin "1") (pinfunction "1_1") (pintype "passive"))
      (node (ref "R18") (pin "1") (pinfunction "1_1") (pintype "passive"))
      (node (ref "R20") (pin "2") (pinfunction "2_2") (pintype "passive"))
      (node (ref "R22") (pin "1") (pinfunction "1_1") (pintype "passive"))
      (node (ref "R3") (pin "1") (pinfunction "1_1") (pintype "passive"))
      (node (ref "R39") (pin "1") (pinfunction "1_1") (pintype "passive"))
      (node (ref "R40") (pin "2") (pinfunction "2_2") (pintype "passive"))
      (node (ref "R9") (pin "1") (pinfunction "1_1") (pintype "passive"))
      (node (ref "RFM95") (pin "13") (pinfunction "VCC_13") (pintype "bidirectional"))
      (node (ref "STM32F103RET6") (pin "1") (pinfunction "VBAT_1") (pintype "power_in"))
      (node (ref "STM32F103RET6") (pin "19") (pinfunction "VDD_4_19") (pintype "power_in"))
      (node (ref "STM32F103RET6") (pin "32") (pinfunction "VDD_1_32") (pintype "power_in"))
      (node (ref "STM32F103RET6") (pin "48") (pinfunction "VDD_2_48") (pintype "power_in"))
      (node (ref "STM32F103RET6") (pin "64") (pinfunction "VDD_3_64") (pintype "power_in"))
    )
    (net (code "79") (name "VDD") (class "Default")
      (node (ref "BAT60JFILM") (pin "C") (pinfunction "C_C") (pintype "passive"))
      (node (ref "IC1") (pin "3") (pinfunction "VIN_3") (pintype "input"))
    )
    (net (code "80") (name "unconnected-(MPU9150-CLKOUT-Pad22)") (class "Default")
      (node (ref "MPU9150") (pin "22") (pinfunction "CLKOUT_22") (pintype "bidirectional"))
    )
    (net (code "81") (name "unconnected-(MS5611-SDO-Pad6)") (class "Default")
      (node (ref "MS5611") (pin "6") (pinfunction "SDO_6") (pintype "output"))
    )
    (net (code "82") (name "unconnected-(STM32F103RET6C-PA4-Pad20)") (class "Default")
      (node (ref "STM32F103RET6") (pin "20") (pinfunction "PA4_20") (pintype "bidirectional"))
    )
    (net (code "83") (name "unconnected-(STM32F103RET6E-PB3-Pad55)") (class "Default")
      (node (ref "STM32F103RET6") (pin "55") (pinfunction "PB3_55") (pintype "bidirectional"))
    )
    (net (code "84") (name "unconnected-(STM32F103RET6F-PC13-Pad2)") (class "Default")
      (node (ref "STM32F103RET6") (pin "2") (pinfunction "PC13_2") (pintype "bidirectional"))
    )
    (net (code "85") (name "unconnected-(STM32F103RET6F-PC14-Pad3)") (class "Default")
      (node (ref "STM32F103RET6") (pin "3") (pinfunction "PC14_3") (pintype "bidirectional"))
    )
    (net (code "86") (name "unconnected-(STM32F103RET6F-PC15-Pad4)") (class "Default")
      (node (ref "STM32F103RET6") (pin "4") (pinfunction "PC15_4") (pintype "bidirectional"))
    )
    (net (code "87") (name "unconnected-(STM32F103RET6H-PD2-Pad54)") (class "Default")
      (node (ref "STM32F103RET6") (pin "54") (pinfunction "PD2_54") (pintype "bidirectional"))
    )
  )
)
